# SX1276Radio.net
KiCad netlist of a schematic drawn in Altium Designer
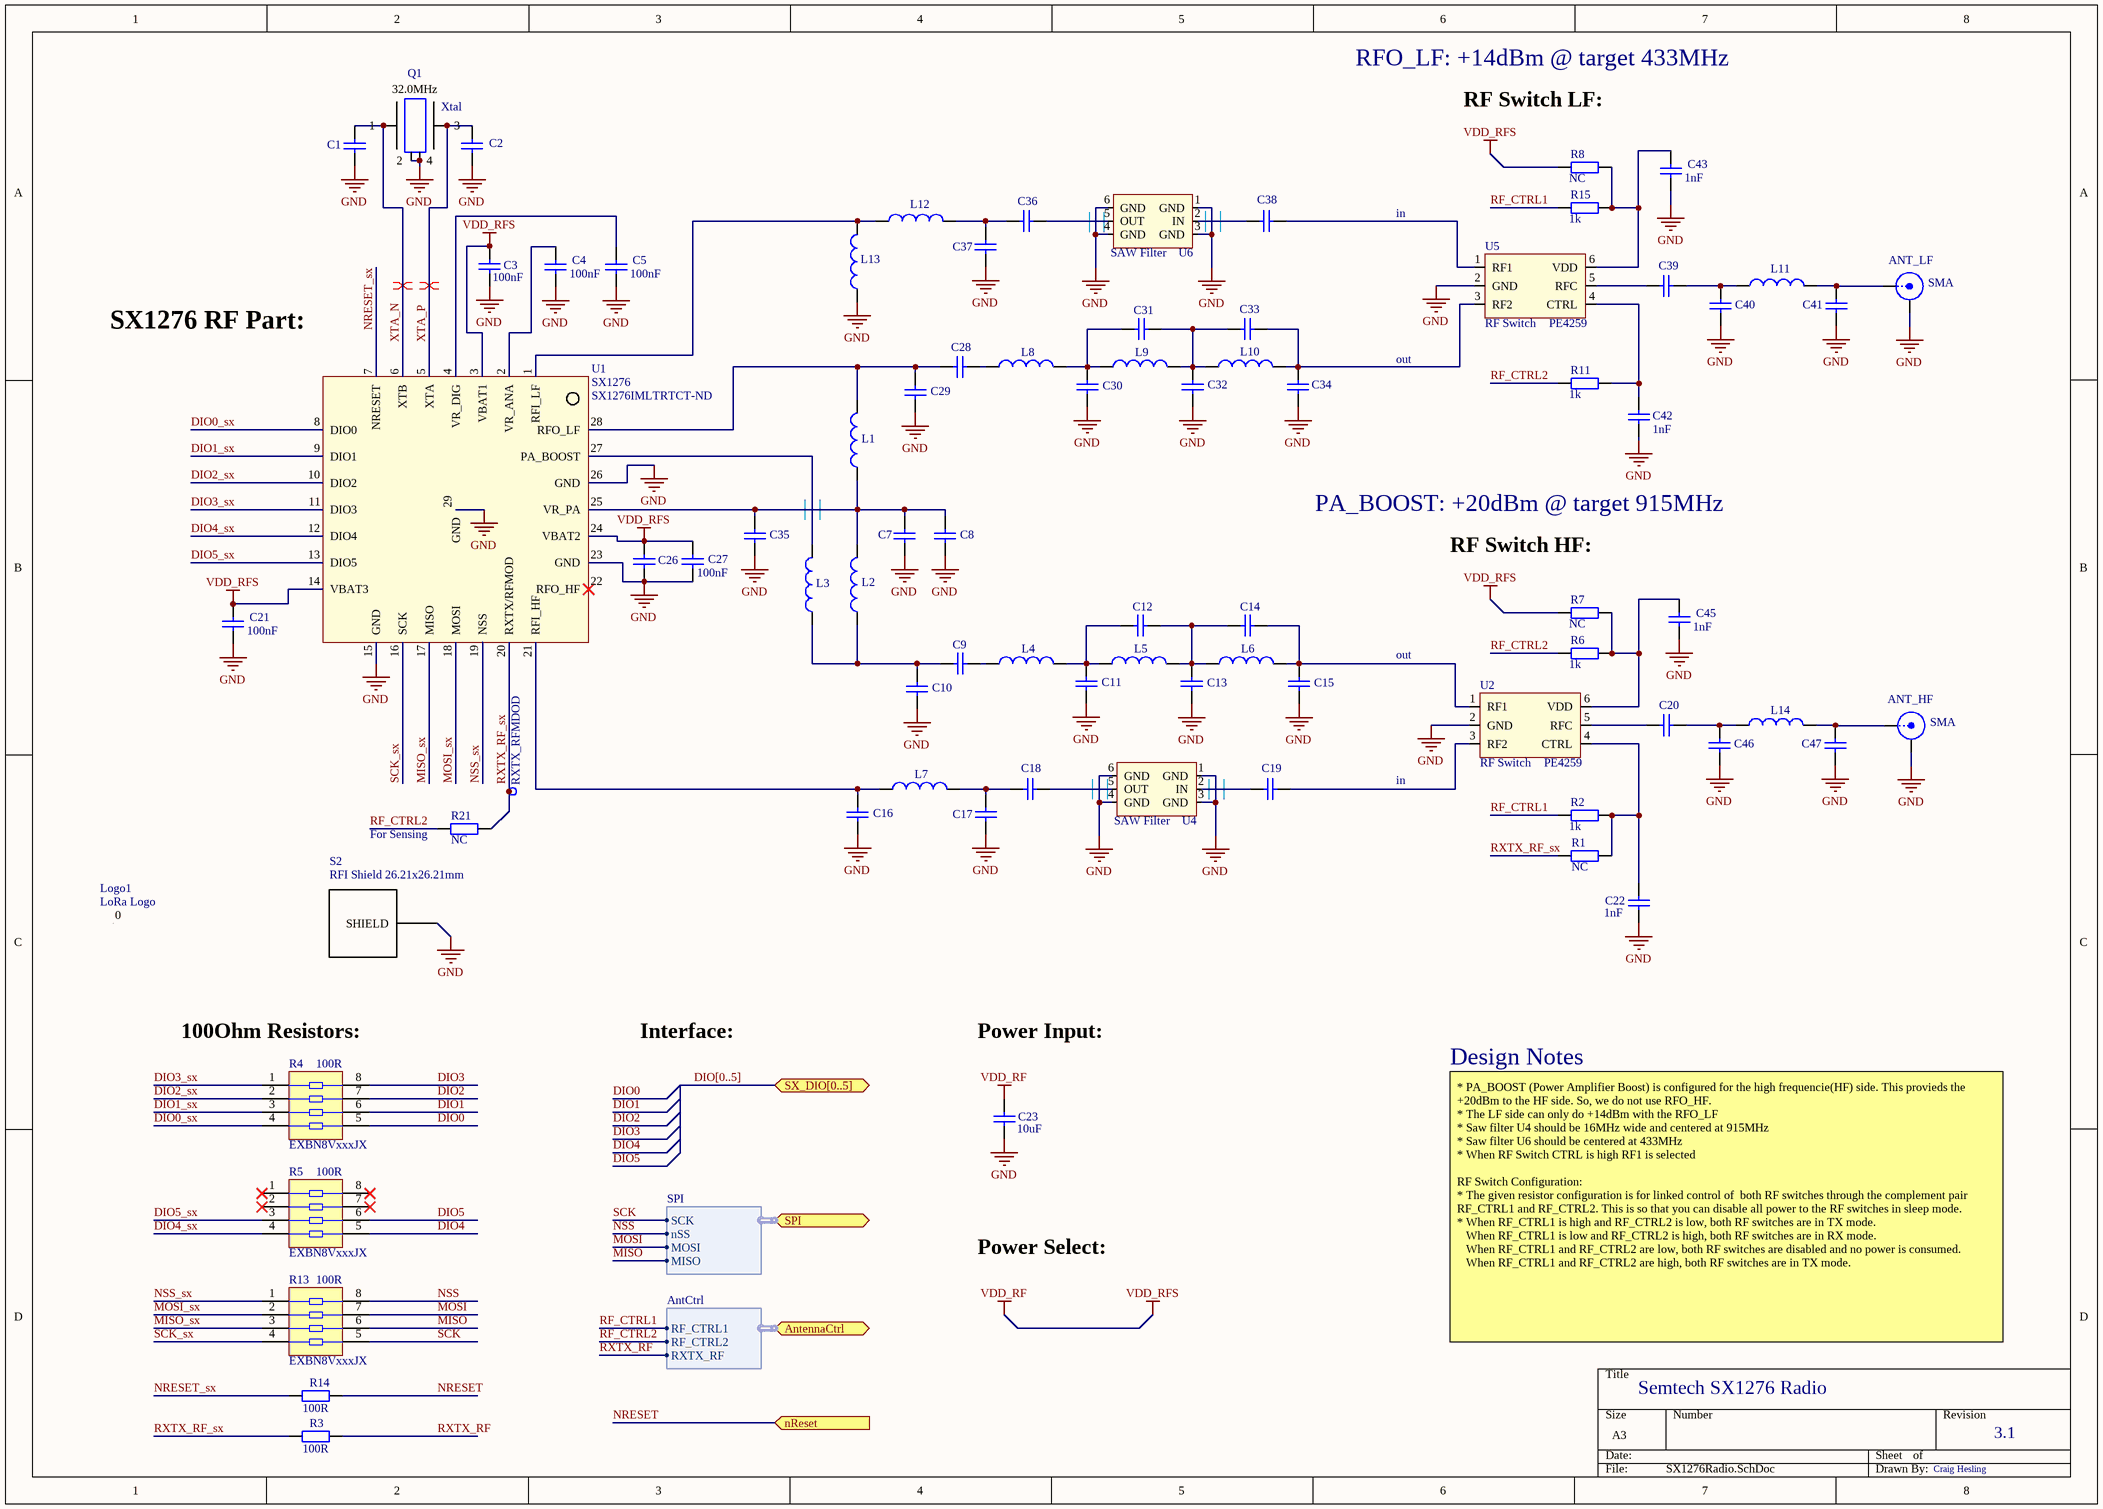
[diagram p0: SX1276Radio.SchDoc]

(export (version "E")
  (design (tool "Eeschema 10.0.6"))
  (components
    (comp (ref "ANT_HF")
      (value "SMA")
      (footprint "SMA END LAUNCH JACK RECEPTACLE SHORT")
      (description "SMA Straight Connector")
      (fields (field (name "PUBLISHER") "Altium Limited"))
      (libsource (lib "SX1276_e268v01a") (part "SMA"))
    )
    (comp (ref "ANT_LF")
      (value "SMA")
      (footprint "SMA END LAUNCH JACK RECEPTACLE SHORT")
      (description "SMA Straight Connector")
      (fields (field (name "PUBLISHER") "Altium Limited"))
      (libsource (lib "SX1276_e268v01a") (part "SMA"))
    )
    (comp (ref "C1")
      (value "Cap")
      (footprint "rlc_402_smd")
      (description "Capacitor SMD")
      (fields (field (name "PUBLISHER") "Altium Limited"))
      (libsource (lib "SX1276_e268v01a") (part "Cap"))
    )
    (comp (ref "C2")
      (value "Cap")
      (footprint "rlc_402_smd")
      (description "Capacitor SMD")
      (fields (field (name "PUBLISHER") "Altium Limited"))
      (libsource (lib "SX1276_e268v01a") (part "Cap"))
    )
    (comp (ref "C3")
      (value "100nF")
      (footprint "rlc_402_smd")
      (description "Capacitor SMD")
      (fields (field (name "Comment") "Cap") (field (name "PUBLISHER") "Altium Limited"))
      (libsource (lib "SX1276_e268v01a") (part "Cap"))
    )
    (comp (ref "C4")
      (value "100nF")
      (footprint "rlc_402_smd")
      (description "Capacitor SMD")
      (fields (field (name "Comment") "Cap") (field (name "PUBLISHER") "Altium Limited"))
      (libsource (lib "SX1276_e268v01a") (part "Cap"))
    )
    (comp (ref "C5")
      (value "100nF")
      (footprint "rlc_402_smd")
      (description "Capacitor SMD")
      (fields (field (name "Comment") "Cap") (field (name "PUBLISHER") "Altium Limited"))
      (libsource (lib "SX1276_e268v01a") (part "Cap"))
    )
    (comp (ref "C7")
      (value "Cap")
      (footprint "rlc_402_smd")
      (description "Capacitor SMD")
      (fields (field (name "PUBLISHER") "Altium Limited"))
      (libsource (lib "SX1276_e268v01a") (part "Cap"))
    )
    (comp (ref "C8")
      (value "Cap")
      (footprint "rlc_402_smd")
      (description "Capacitor SMD")
      (fields (field (name "PUBLISHER") "Altium Limited"))
      (libsource (lib "SX1276_e268v01a") (part "Cap"))
    )
    (comp (ref "C9")
      (value "Cap")
      (footprint "rlc_402_smd")
      (description "Capacitor SMD")
      (fields (field (name "PUBLISHER") "Altium Limited"))
      (libsource (lib "SX1276_e268v01a") (part "Cap"))
    )
    (comp (ref "C10")
      (value "Cap")
      (footprint "rlc_402_smd")
      (description "Capacitor SMD")
      (fields (field (name "PUBLISHER") "Altium Limited"))
      (libsource (lib "SX1276_e268v01a") (part "Cap"))
    )
    (comp (ref "C11")
      (value "Cap")
      (footprint "rlc_402_smd")
      (description "Capacitor SMD")
      (fields (field (name "PUBLISHER") "Altium Limited"))
      (libsource (lib "SX1276_e268v01a") (part "Cap"))
    )
    (comp (ref "C12")
      (value "Cap")
      (footprint "rlc_402_smd")
      (description "Capacitor SMD")
      (fields (field (name "PUBLISHER") "Altium Limited"))
      (libsource (lib "SX1276_e268v01a") (part "Cap"))
    )
    (comp (ref "C13")
      (value "Cap")
      (footprint "rlc_402_smd")
      (description "Capacitor SMD")
      (fields (field (name "PUBLISHER") "Altium Limited"))
      (libsource (lib "SX1276_e268v01a") (part "Cap"))
    )
    (comp (ref "C14")
      (value "Cap")
      (footprint "rlc_402_smd")
      (description "Capacitor SMD")
      (fields (field (name "PUBLISHER") "Altium Limited"))
      (libsource (lib "SX1276_e268v01a") (part "Cap"))
    )
    (comp (ref "C15")
      (value "Cap")
      (footprint "rlc_402_smd")
      (description "Capacitor SMD")
      (fields (field (name "PUBLISHER") "Altium Limited"))
      (libsource (lib "SX1276_e268v01a") (part "Cap"))
    )
    (comp (ref "C16")
      (value "Cap")
      (footprint "rlc_402_smd")
      (description "Capacitor SMD")
      (fields (field (name "PUBLISHER") "Altium Limited"))
      (libsource (lib "SX1276_e268v01a") (part "Cap"))
    )
    (comp (ref "C17")
      (value "Cap")
      (footprint "rlc_402_smd")
      (description "Capacitor SMD")
      (fields (field (name "PUBLISHER") "Altium Limited"))
      (libsource (lib "SX1276_e268v01a") (part "Cap"))
    )
    (comp (ref "C18")
      (value "Cap")
      (footprint "rlc_402_smd")
      (description "Capacitor SMD")
      (fields (field (name "PUBLISHER") "Altium Limited"))
      (libsource (lib "SX1276_e268v01a") (part "Cap"))
    )
    (comp (ref "C19")
      (value "Cap")
      (footprint "rlc_402_smd")
      (description "Capacitor SMD")
      (fields (field (name "PUBLISHER") "Altium Limited"))
      (libsource (lib "SX1276_e268v01a") (part "Cap"))
    )
    (comp (ref "C20")
      (value "Cap")
      (footprint "rlc_402_smd")
      (description "Capacitor SMD")
      (fields (field (name "PUBLISHER") "Altium Limited"))
      (libsource (lib "SX1276_e268v01a") (part "Cap"))
    )
    (comp (ref "C21")
      (value "100nF")
      (footprint "rlc_402_smd")
      (description "Capacitor SMD")
      (fields (field (name "Comment") "Cap") (field (name "PUBLISHER") "Altium Limited"))
      (libsource (lib "SX1276_e268v01a") (part "Cap"))
    )
    (comp (ref "C22")
      (value "1nF")
      (footprint "rlc_402_smd")
      (description "Capacitor SMD")
      (fields (field (name "Comment") "Cap") (field (name "PUBLISHER") "Altium Limited"))
      (libsource (lib "SX1276_e268v01a") (part "Cap"))
    )
    (comp (ref "C23")
      (value "10uF")
      (footprint "rlc_805_smd")
      (description "Capacitor SMD")
      (fields (field (name "Comment") "Cap") (field (name "PUBLISHER") "Altium Limited"))
      (libsource (lib "SX1276_e268v01a") (part "Cap"))
    )
    (comp (ref "C26")
      (value "Cap")
      (footprint "rlc_402_smd")
      (description "Capacitor SMD")
      (fields (field (name "PUBLISHER") "Altium Limited"))
      (libsource (lib "SX1276_e268v01a") (part "Cap"))
    )
    (comp (ref "C27")
      (value "100nF")
      (footprint "rlc_402_smd")
      (description "Capacitor SMD")
      (fields (field (name "Comment") "Cap") (field (name "PUBLISHER") "Altium Limited"))
      (libsource (lib "SX1276_e268v01a") (part "Cap"))
    )
    (comp (ref "C28")
      (value "Cap")
      (footprint "rlc_402_smd")
      (description "Capacitor SMD")
      (fields (field (name "PUBLISHER") "Altium Limited"))
      (libsource (lib "SX1276_e268v01a") (part "Cap"))
    )
    (comp (ref "C29")
      (value "Cap")
      (footprint "rlc_402_smd")
      (description "Capacitor SMD")
      (fields (field (name "PUBLISHER") "Altium Limited"))
      (libsource (lib "SX1276_e268v01a") (part "Cap"))
    )
    (comp (ref "C30")
      (value "Cap")
      (footprint "rlc_402_smd")
      (description "Capacitor SMD")
      (fields (field (name "PUBLISHER") "Altium Limited"))
      (libsource (lib "SX1276_e268v01a") (part "Cap"))
    )
    (comp (ref "C31")
      (value "Cap")
      (footprint "rlc_402_smd")
      (description "Capacitor SMD")
      (fields (field (name "PUBLISHER") "Altium Limited"))
      (libsource (lib "SX1276_e268v01a") (part "Cap"))
    )
    (comp (ref "C32")
      (value "Cap")
      (footprint "rlc_402_smd")
      (description "Capacitor SMD")
      (fields (field (name "PUBLISHER") "Altium Limited"))
      (libsource (lib "SX1276_e268v01a") (part "Cap"))
    )
    (comp (ref "C33")
      (value "Cap")
      (footprint "rlc_402_smd")
      (description "Capacitor SMD")
      (fields (field (name "PUBLISHER") "Altium Limited"))
      (libsource (lib "SX1276_e268v01a") (part "Cap"))
    )
    (comp (ref "C34")
      (value "Cap")
      (footprint "rlc_402_smd")
      (description "Capacitor SMD")
      (fields (field (name "PUBLISHER") "Altium Limited"))
      (libsource (lib "SX1276_e268v01a") (part "Cap"))
    )
    (comp (ref "C35")
      (value "Cap")
      (footprint "rlc_402_smd")
      (description "Capacitor SMD")
      (fields (field (name "PUBLISHER") "Altium Limited"))
      (libsource (lib "SX1276_e268v01a") (part "Cap"))
    )
    (comp (ref "C36")
      (value "Cap")
      (footprint "rlc_402_smd")
      (description "Capacitor SMD")
      (fields (field (name "PUBLISHER") "Altium Limited"))
      (libsource (lib "SX1276_e268v01a") (part "Cap"))
    )
    (comp (ref "C37")
      (value "Cap")
      (footprint "rlc_402_smd")
      (description "Capacitor SMD")
      (fields (field (name "PUBLISHER") "Altium Limited"))
      (libsource (lib "SX1276_e268v01a") (part "Cap"))
    )
    (comp (ref "C38")
      (value "Cap")
      (footprint "rlc_402_smd")
      (description "Capacitor SMD")
      (fields (field (name "PUBLISHER") "Altium Limited"))
      (libsource (lib "SX1276_e268v01a") (part "Cap"))
    )
    (comp (ref "C39")
      (value "Cap")
      (footprint "rlc_402_smd")
      (description "Capacitor SMD")
      (fields (field (name "PUBLISHER") "Altium Limited"))
      (libsource (lib "SX1276_e268v01a") (part "Cap"))
    )
    (comp (ref "C40")
      (value "Cap")
      (footprint "rlc_402_smd")
      (description "Capacitor SMD")
      (fields (field (name "PUBLISHER") "Altium Limited"))
      (libsource (lib "SX1276_e268v01a") (part "Cap"))
    )
    (comp (ref "C41")
      (value "Cap")
      (footprint "rlc_402_smd")
      (description "Capacitor SMD")
      (fields (field (name "PUBLISHER") "Altium Limited"))
      (libsource (lib "SX1276_e268v01a") (part "Cap"))
    )
    (comp (ref "C42")
      (value "1nF")
      (footprint "rlc_402_smd")
      (description "Capacitor SMD")
      (fields (field (name "Comment") "Cap") (field (name "PUBLISHER") "Altium Limited"))
      (libsource (lib "SX1276_e268v01a") (part "Cap"))
    )
    (comp (ref "C43")
      (value "1nF")
      (footprint "rlc_402_smd")
      (description "Capacitor SMD")
      (fields (field (name "Comment") "Cap") (field (name "PUBLISHER") "Altium Limited"))
      (libsource (lib "SX1276_e268v01a") (part "Cap"))
    )
    (comp (ref "C45")
      (value "1nF")
      (footprint "rlc_402_smd")
      (description "Capacitor SMD")
      (fields (field (name "Comment") "Cap") (field (name "PUBLISHER") "Altium Limited"))
      (libsource (lib "SX1276_e268v01a") (part "Cap"))
    )
    (comp (ref "C46")
      (value "Cap")
      (footprint "rlc_402_smd")
      (description "Capacitor SMD")
      (fields (field (name "PUBLISHER") "Altium Limited"))
      (libsource (lib "SX1276_e268v01a") (part "Cap"))
    )
    (comp (ref "C47")
      (value "Cap")
      (footprint "rlc_402_smd")
      (description "Capacitor SMD")
      (fields (field (name "PUBLISHER") "Altium Limited"))
      (libsource (lib "SX1276_e268v01a") (part "Cap"))
    )
    (comp (ref "L1")
      (value "Inductor")
      (footprint "rlc_402_smd")
      (description "Inductor SMD")
      (fields (field (name "PUBLISHER") "Altium Limited"))
      (libsource (lib "SX1276_e268v01a") (part "Inductor"))
    )
    (comp (ref "L2")
      (value "Inductor")
      (footprint "rlc_402_smd")
      (description "Inductor SMD")
      (fields (field (name "PUBLISHER") "Altium Limited"))
      (libsource (lib "SX1276_e268v01a") (part "Inductor"))
    )
    (comp (ref "L3")
      (value "Inductor")
      (footprint "rlc_402_smd")
      (description "Inductor SMD")
      (fields (field (name "PUBLISHER") "Altium Limited"))
      (libsource (lib "SX1276_e268v01a") (part "Inductor"))
    )
    (comp (ref "L4")
      (value "Inductor")
      (footprint "rlc_402_smd")
      (description "Inductor SMD")
      (fields (field (name "PUBLISHER") "Altium Limited"))
      (libsource (lib "SX1276_e268v01a") (part "Inductor"))
    )
    (comp (ref "L5")
      (value "Inductor")
      (footprint "rlc_402_smd")
      (description "Inductor SMD")
      (fields (field (name "PUBLISHER") "Altium Limited"))
      (libsource (lib "SX1276_e268v01a") (part "Inductor"))
    )
    (comp (ref "L6")
      (value "Inductor")
      (footprint "rlc_402_smd")
      (description "Inductor SMD")
      (fields (field (name "PUBLISHER") "Altium Limited"))
      (libsource (lib "SX1276_e268v01a") (part "Inductor"))
    )
    (comp (ref "L7")
      (value "Inductor")
      (footprint "rlc_402_smd")
      (description "Inductor SMD")
      (fields (field (name "PUBLISHER") "Altium Limited"))
      (libsource (lib "SX1276_e268v01a") (part "Inductor"))
    )
    (comp (ref "L8")
      (value "Inductor")
      (footprint "rlc_402_smd")
      (description "Inductor SMD")
      (fields (field (name "PUBLISHER") "Altium Limited"))
      (libsource (lib "SX1276_e268v01a") (part "Inductor"))
    )
    (comp (ref "L9")
      (value "Inductor")
      (footprint "rlc_402_smd")
      (description "Inductor SMD")
      (fields (field (name "PUBLISHER") "Altium Limited"))
      (libsource (lib "SX1276_e268v01a") (part "Inductor"))
    )
    (comp (ref "L10")
      (value "Inductor")
      (footprint "rlc_402_smd")
      (description "Inductor SMD")
      (fields (field (name "PUBLISHER") "Altium Limited"))
      (libsource (lib "SX1276_e268v01a") (part "Inductor"))
    )
    (comp (ref "L11")
      (value "Inductor")
      (footprint "rlc_402_smd")
      (description "Inductor SMD")
      (fields (field (name "PUBLISHER") "Altium Limited"))
      (libsource (lib "SX1276_e268v01a") (part "Inductor"))
    )
    (comp (ref "L12")
      (value "Inductor")
      (footprint "rlc_402_smd")
      (description "Inductor SMD")
      (fields (field (name "PUBLISHER") "Altium Limited"))
      (libsource (lib "SX1276_e268v01a") (part "Inductor"))
    )
    (comp (ref "L13")
      (value "Inductor")
      (footprint "rlc_402_smd")
      (description "Inductor SMD")
      (fields (field (name "PUBLISHER") "Altium Limited"))
      (libsource (lib "SX1276_e268v01a") (part "Inductor"))
    )
    (comp (ref "L14")
      (value "Inductor")
      (footprint "rlc_402_smd")
      (description "Inductor SMD")
      (fields (field (name "PUBLISHER") "Altium Limited"))
      (libsource (lib "SX1276_e268v01a") (part "Inductor"))
    )
    (comp (ref "Logo1")
      (value "LoRa Logo")
      (footprint "Logo LoRa Size1")
      (description "Schematic symbol for Logo")
      (libsource (lib "SX1276_e268v01a") (part "Logo"))
    )
    (comp (ref "Q1")
      (value "Xtal")
      (footprint "nd3225da - nd2520da")
      (description "Crystal with GND pins")
      (fields (field (name "ALTIUM_VALUE") "32.0MHz"))
      (libsource (lib "SX1276_e268v01a") (part "Xtal GND"))
    )
    (comp (ref "R1")
      (value "NC")
      (footprint "rlc_402_smd")
      (description "Resistor SMD - IEC symbol version")
      (fields (field (name "Comment") "Resistor"))
      (libsource (lib "") (part "Resistor_2"))
    )
    (comp (ref "R2")
      (value "1k")
      (footprint "rlc_402_smd")
      (description "Resistor SMD - IEC symbol version")
      (fields (field (name "Comment") "Resistor"))
      (libsource (lib "SX1276_e268v01a") (part "Resistor"))
    )
    (comp (ref "R3")
      (value "100R")
      (footprint "rlc_402_smd")
      (description "Resistor SMD - IEC symbol version")
      (fields (field (name "Comment") "Resistor"))
      (libsource (lib "") (part "Resistor_1"))
    )
    (comp (ref "R4")
      (value "EXBN8VxxxJX")
      (footprint "EXB28V")
      (description "Mini-Flat Package, Isolated Resistor Network, 0.031 W/resistor")
      (fields (field (name "ALTIUM_VALUE") "100R"))
      (libsource (lib "SX1276_e268v01a") (part "EXBN8VxxxJX"))
    )
    (comp (ref "R5")
      (value "EXBN8VxxxJX")
      (footprint "EXB28V")
      (description "Mini-Flat Package, Isolated Resistor Network, 0.031 W/resistor")
      (fields (field (name "ALTIUM_VALUE") "100R"))
      (libsource (lib "SX1276_e268v01a") (part "EXBN8VxxxJX"))
    )
    (comp (ref "R6")
      (value "1k")
      (footprint "rlc_402_smd")
      (description "Resistor SMD - IEC symbol version")
      (fields (field (name "Comment") "Resistor"))
      (libsource (lib "SX1276_e268v01a") (part "Resistor"))
    )
    (comp (ref "R7")
      (value "NC")
      (footprint "rlc_402_smd")
      (description "Resistor SMD - IEC symbol version")
      (fields (field (name "Comment") "Resistor"))
      (libsource (lib "SX1276_e268v01a") (part "Resistor"))
    )
    (comp (ref "R8")
      (value "NC")
      (footprint "rlc_402_smd")
      (description "Resistor SMD - IEC symbol version")
      (fields (field (name "Comment") "Resistor"))
      (libsource (lib "SX1276_e268v01a") (part "Resistor"))
    )
    (comp (ref "R11")
      (value "1k")
      (footprint "rlc_402_smd")
      (description "Resistor SMD - IEC symbol version")
      (fields (field (name "Comment") "Resistor"))
      (libsource (lib "SX1276_e268v01a") (part "Resistor"))
    )
    (comp (ref "R13")
      (value "EXBN8VxxxJX")
      (footprint "EXB28V")
      (description "Mini-Flat Package, Isolated Resistor Network, 0.031 W/resistor")
      (fields (field (name "ALTIUM_VALUE") "100R"))
      (libsource (lib "SX1276_e268v01a") (part "EXBN8VxxxJX"))
    )
    (comp (ref "R14")
      (value "100R")
      (footprint "rlc_402_smd")
      (description "Resistor SMD - IEC symbol version")
      (fields (field (name "Comment") "Resistor"))
      (libsource (lib "") (part "Resistor_1"))
    )
    (comp (ref "R15")
      (value "1k")
      (footprint "rlc_402_smd")
      (description "Resistor SMD - IEC symbol version")
      (fields (field (name "Comment") "Resistor"))
      (libsource (lib "SX1276_e268v01a") (part "Resistor"))
    )
    (comp (ref "R21")
      (value "NC")
      (footprint "rlc_402_smd")
      (description "Resistor SMD - IEC symbol version")
      (fields (field (name "Comment") "Resistor"))
      (libsource (lib "SX1276_e268v01a") (part "Resistor"))
    )
    (comp (ref "RXTX_RFMDOD")
      (value "Test Pin")
      (footprint "pin_SMD")
      (libsource (lib "SX1276_e268v01a") (part "test_pin"))
    )
    (comp (ref "S2")
      (value "RFI Shield 26.21x26.21mm")
      (footprint "RFI_SHIELD_26.21x26.21MM_Padded")
      (libsource (lib "ExtraComponents") (part "RFI_SHIELD_26.21x26.21mm"))
    )
    (comp (ref "U1")
      (value "SX1276")
      (footprint "vqfn28_6x6mm_big_vias")
      (description "SX1276 - Low Power Integrated UHF Transceiver with loRa Modem")
      (fields (field (name "SUPPLIER PART NUMBER 1") "SX1276IMLTRTCT-ND"))
      (libsource (lib "SX1276_e268v01a") (part "SX1276"))
    )
    (comp (ref "U2")
      (value "RF Switch")
      (footprint "SC70-6")
      (description "PE4259 Peregrine RF Switch")
      (fields (field (name "ALTIUM_VALUE") "PE4259"))
      (libsource (lib "SX1276_e268v01a") (part "PE4259 RF Switch"))
    )
    (comp (ref "U4")
      (value "SAW Filter")
      (footprint "DCC6C_3.0x3.0mm")
      (description "SAW Filter - Bandpass - TEMEX type")
      (libsource (lib "SX1276_e268v01a") (part "SAW Filter"))
    )
    (comp (ref "U5")
      (value "RF Switch")
      (footprint "SC70-6")
      (description "PE4259 Peregrine RF Switch")
      (fields (field (name "ALTIUM_VALUE") "PE4259"))
      (libsource (lib "SX1276_e268v01a") (part "PE4259 RF Switch"))
    )
    (comp (ref "U6")
      (value "SAW Filter")
      (footprint "DCC6C_3.0x3.0mm")
      (description "SAW Filter - Bandpass - TEMEX type")
      (libsource (lib "SX1276_e268v01a") (part "SAW Filter"))
    )
  )
  (nets
    (net (code "3") (name "/DIO0") (class "Default")
      (node (ref "R4") (pin "5") (pinfunction "5_5") (pintype "passive"))
    )
    (net (code "4") (name "/DIO0_sx") (class "Default")
      (node (ref "R4") (pin "4") (pinfunction "4_4") (pintype "passive"))
      (node (ref "U1") (pin "8") (pinfunction "DIO0_8") (pintype "passive"))
    )
    (net (code "5") (name "/DIO1") (class "Default")
      (node (ref "R4") (pin "6") (pinfunction "6_6") (pintype "passive"))
    )
    (net (code "6") (name "/DIO1_sx") (class "Default")
      (node (ref "R4") (pin "3") (pinfunction "3_3") (pintype "passive"))
      (node (ref "U1") (pin "9") (pinfunction "DIO1_9") (pintype "passive"))
    )
    (net (code "7") (name "/DIO2") (class "Default")
      (node (ref "R4") (pin "7") (pinfunction "7_7") (pintype "passive"))
    )
    (net (code "8") (name "/DIO2_sx") (class "Default")
      (node (ref "R4") (pin "2") (pinfunction "2_2") (pintype "passive"))
      (node (ref "U1") (pin "10") (pinfunction "DIO2_10") (pintype "passive"))
    )
    (net (code "9") (name "/DIO3") (class "Default")
      (node (ref "R4") (pin "8") (pinfunction "8_8") (pintype "passive"))
    )
    (net (code "10") (name "/DIO3_sx") (class "Default")
      (node (ref "R4") (pin "1") (pinfunction "1_1") (pintype "passive"))
      (node (ref "U1") (pin "11") (pinfunction "DIO3_11") (pintype "passive"))
    )
    (net (code "11") (name "/DIO4") (class "Default")
      (node (ref "R5") (pin "5") (pinfunction "5_5") (pintype "passive"))
    )
    (net (code "12") (name "/DIO4_sx") (class "Default")
      (node (ref "R5") (pin "4") (pinfunction "4_4") (pintype "passive"))
      (node (ref "U1") (pin "12") (pinfunction "DIO4_12") (pintype "passive"))
    )
    (net (code "13") (name "/DIO5") (class "Default")
      (node (ref "R5") (pin "6") (pinfunction "6_6") (pintype "passive"))
    )
    (net (code "14") (name "/DIO5_sx") (class "Default")
      (node (ref "R5") (pin "3") (pinfunction "3_3") (pintype "passive"))
      (node (ref "U1") (pin "13") (pinfunction "DIO5_13") (pintype "passive"))
    )
    (net (code "16") (name "/MISO") (class "Default")
      (node (ref "R13") (pin "6") (pinfunction "6_6") (pintype "passive"))
    )
    (net (code "17") (name "/MISO_sx") (class "Default")
      (node (ref "R13") (pin "3") (pinfunction "3_3") (pintype "passive"))
      (node (ref "U1") (pin "17") (pinfunction "MISO_17") (pintype "passive"))
    )
    (net (code "18") (name "/MOSI") (class "Default")
      (node (ref "R13") (pin "7") (pinfunction "7_7") (pintype "passive"))
    )
    (net (code "19") (name "/MOSI_sx") (class "Default")
      (node (ref "R13") (pin "2") (pinfunction "2_2") (pintype "passive"))
      (node (ref "U1") (pin "18") (pinfunction "MOSI_18") (pintype "passive"))
    )
    (net (code "20") (name "/NRESET") (class "Default")
      (node (ref "R14") (pin "2") (pinfunction "2_2") (pintype "passive"))
    )
    (net (code "21") (name "/NRESET_sx") (class "Default")
      (node (ref "R14") (pin "1") (pinfunction "1_1") (pintype "passive"))
      (node (ref "U1") (pin "7") (pinfunction "NRESET_7") (pintype "passive"))
    )
    (net (code "22") (name "/NSS") (class "Default")
      (node (ref "R13") (pin "8") (pinfunction "8_8") (pintype "passive"))
    )
    (net (code "23") (name "/NSS_sx") (class "Default")
      (node (ref "R13") (pin "1") (pinfunction "1_1") (pintype "passive"))
      (node (ref "U1") (pin "19") (pinfunction "NSS_19") (pintype "passive"))
    )
    (net (code "24") (name "/RF_CTRL1") (class "Default")
      (node (ref "R15") (pin "2") (pinfunction "2_2") (pintype "passive"))
      (node (ref "R2") (pin "2") (pinfunction "2_2") (pintype "passive"))
    )
    (net (code "25") (name "/RF_CTRL2") (class "Default")
      (node (ref "R11") (pin "2") (pinfunction "2_2") (pintype "passive"))
      (node (ref "R21") (pin "2") (pinfunction "2_2") (pintype "passive"))
      (node (ref "R6") (pin "2") (pinfunction "2_2") (pintype "passive"))
    )
    (net (code "26") (name "/RXTX_RF") (class "Default")
      (node (ref "R3") (pin "2") (pinfunction "2_2") (pintype "passive"))
    )
    (net (code "27") (name "/RXTX_RF_sx") (class "Default")
      (node (ref "R1") (pin "1") (pinfunction "1_1") (pintype "passive"))
      (node (ref "R21") (pin "1") (pinfunction "1_1") (pintype "passive"))
      (node (ref "R3") (pin "1") (pinfunction "1_1") (pintype "passive"))
      (node (ref "RXTX_RFMDOD") (pin "1") (pinfunction "pin_1") (pintype "passive"))
      (node (ref "U1") (pin "20") (pinfunction "RXTX/RFMOD_20") (pintype "passive"))
    )
    (net (code "28") (name "/SCK") (class "Default")
      (node (ref "R13") (pin "5") (pinfunction "5_5") (pintype "passive"))
    )
    (net (code "29") (name "/SCK_sx") (class "Default")
      (node (ref "R13") (pin "4") (pinfunction "4_4") (pintype "passive"))
      (node (ref "U1") (pin "16") (pinfunction "SCK_16") (pintype "passive"))
    )
    (net (code "30") (name "/XTA_N") (class "Default")
      (node (ref "C1") (pin "2") (pinfunction "2_2") (pintype "passive"))
      (node (ref "Q1") (pin "1") (pinfunction "1_1") (pintype "passive"))
      (node (ref "U1") (pin "6") (pinfunction "XTB_6") (pintype "passive"))
    )
    (net (code "31") (name "/XTA_P") (class "Default")
      (node (ref "C2") (pin "2") (pinfunction "2_2") (pintype "passive"))
      (node (ref "Q1") (pin "3") (pinfunction "3_3") (pintype "passive"))
      (node (ref "U1") (pin "5") (pinfunction "XTA_5") (pintype "passive"))
    )
    (net (code "34") (name "GND") (class "Default")
      (node (ref "ANT_HF") (pin "2") (pinfunction "GND_2") (pintype "passive"))
      (node (ref "ANT_LF") (pin "2") (pinfunction "GND_2") (pintype "passive"))
      (node (ref "C1") (pin "1") (pinfunction "1_1") (pintype "passive"))
      (node (ref "C10") (pin "1") (pinfunction "1_1") (pintype "passive"))
      (node (ref "C11") (pin "1") (pinfunction "1_1") (pintype "passive"))
      (node (ref "C13") (pin "1") (pinfunction "1_1") (pintype "passive"))
      (node (ref "C15") (pin "1") (pinfunction "1_1") (pintype "passive"))
      (node (ref "C16") (pin "1") (pinfunction "1_1") (pintype "passive"))
      (node (ref "C17") (pin "1") (pinfunction "1_1") (pintype "passive"))
      (node (ref "C2") (pin "1") (pinfunction "1_1") (pintype "passive"))
      (node (ref "C21") (pin "1") (pinfunction "1_1") (pintype "passive"))
      (node (ref "C22") (pin "2") (pinfunction "2_2") (pintype "passive"))
      (node (ref "C23") (pin "1") (pinfunction "1_1") (pintype "passive"))
      (node (ref "C26") (pin "1") (pinfunction "1_1") (pintype "passive"))
      (node (ref "C27") (pin "1") (pinfunction "1_1") (pintype "passive"))
      (node (ref "C29") (pin "1") (pinfunction "1_1") (pintype "passive"))
      (node (ref "C3") (pin "1") (pinfunction "1_1") (pintype "passive"))
      (node (ref "C30") (pin "1") (pinfunction "1_1") (pintype "passive"))
      (node (ref "C32") (pin "1") (pinfunction "1_1") (pintype "passive"))
      (node (ref "C34") (pin "1") (pinfunction "1_1") (pintype "passive"))
      (node (ref "C35") (pin "1") (pinfunction "1_1") (pintype "passive"))
      (node (ref "C37") (pin "1") (pinfunction "1_1") (pintype "passive"))
      (node (ref "C4") (pin "1") (pinfunction "1_1") (pintype "passive"))
      (node (ref "C40") (pin "1") (pinfunction "1_1") (pintype "passive"))
      (node (ref "C41") (pin "1") (pinfunction "1_1") (pintype "passive"))
      (node (ref "C42") (pin "2") (pinfunction "2_2") (pintype "passive"))
      (node (ref "C43") (pin "1") (pinfunction "1_1") (pintype "passive"))
      (node (ref "C45") (pin "1") (pinfunction "1_1") (pintype "passive"))
      (node (ref "C46") (pin "1") (pinfunction "1_1") (pintype "passive"))
      (node (ref "C47") (pin "1") (pinfunction "1_1") (pintype "passive"))
      (node (ref "C5") (pin "1") (pinfunction "1_1") (pintype "passive"))
      (node (ref "C7") (pin "1") (pinfunction "1_1") (pintype "passive"))
      (node (ref "C8") (pin "1") (pinfunction "1_1") (pintype "passive"))
      (node (ref "L13") (pin "1") (pinfunction "1_1") (pintype "passive"))
      (node (ref "Q1") (pin "2") (pinfunction "2_2") (pintype "passive"))
      (node (ref "Q1") (pin "4") (pinfunction "4_4") (pintype "passive"))
      (node (ref "S2") (pin "SHIELD") (pinfunction "SHIELD_SHIELD") (pintype "passive"))
      (node (ref "U1") (pin "15") (pinfunction "GND_15") (pintype "passive"))
      (node (ref "U1") (pin "23") (pinfunction "GND_23") (pintype "passive"))
      (node (ref "U1") (pin "26") (pinfunction "GND_26") (pintype "passive"))
      (node (ref "U1") (pin "29") (pinfunction "GND_29") (pintype "passive"))
      (node (ref "U2") (pin "2") (pinfunction "GND_2") (pintype "passive"))
      (node (ref "U4") (pin "1") (pinfunction "GND_1") (pintype "passive"))
      (node (ref "U4") (pin "3") (pinfunction "GND_3") (pintype "passive"))
      (node (ref "U4") (pin "4") (pinfunction "GND_4") (pintype "passive"))
      (node (ref "U4") (pin "6") (pinfunction "GND_6") (pintype "passive"))
      (node (ref "U5") (pin "2") (pinfunction "GND_2") (pintype "passive"))
      (node (ref "U6") (pin "1") (pinfunction "GND_1") (pintype "passive"))
      (node (ref "U6") (pin "3") (pinfunction "GND_3") (pintype "passive"))
      (node (ref "U6") (pin "4") (pinfunction "GND_4") (pintype "passive"))
      (node (ref "U6") (pin "6") (pinfunction "GND_6") (pintype "passive"))
    )
    (net (code "35") (name "Net-(ANT_HF-Signal)") (class "Default")
      (node (ref "ANT_HF") (pin "1") (pinfunction "Signal_1") (pintype "passive"))
      (node (ref "C47") (pin "2") (pinfunction "2_2") (pintype "passive"))
      (node (ref "L14") (pin "2") (pinfunction "2_2") (pintype "passive"))
    )
    (net (code "36") (name "Net-(ANT_LF-Signal)") (class "Default")
      (node (ref "ANT_LF") (pin "1") (pinfunction "Signal_1") (pintype "passive"))
      (node (ref "C41") (pin "2") (pinfunction "2_2") (pintype "passive"))
      (node (ref "L11") (pin "2") (pinfunction "2_2") (pintype "passive"))
    )
    (net (code "37") (name "Net-(C9-Pad1)") (class "Default")
      (node (ref "C9") (pin "1") (pinfunction "1_1") (pintype "passive"))
      (node (ref "L4") (pin "1") (pinfunction "1_1") (pintype "passive"))
    )
    (net (code "38") (name "Net-(C10-Pad2)") (class "Default")
      (node (ref "C10") (pin "2") (pinfunction "2_2") (pintype "passive"))
      (node (ref "C9") (pin "2") (pinfunction "2_2") (pintype "passive"))
      (node (ref "L2") (pin "1") (pinfunction "1_1") (pintype "passive"))
      (node (ref "L3") (pin "1") (pinfunction "1_1") (pintype "passive"))
    )
    (net (code "39") (name "Net-(C11-Pad2)") (class "Default")
      (node (ref "C11") (pin "2") (pinfunction "2_2") (pintype "passive"))
      (node (ref "C12") (pin "2") (pinfunction "2_2") (pintype "passive"))
      (node (ref "L4") (pin "2") (pinfunction "2_2") (pintype "passive"))
      (node (ref "L5") (pin "1") (pinfunction "1_1") (pintype "passive"))
    )
    (net (code "40") (name "Net-(C12-Pad1)") (class "Default")
      (node (ref "C12") (pin "1") (pinfunction "1_1") (pintype "passive"))
      (node (ref "C13") (pin "2") (pinfunction "2_2") (pintype "passive"))
      (node (ref "C14") (pin "2") (pinfunction "2_2") (pintype "passive"))
      (node (ref "L5") (pin "2") (pinfunction "2_2") (pintype "passive"))
      (node (ref "L6") (pin "1") (pinfunction "1_1") (pintype "passive"))
    )
    (net (code "41") (name "Net-(C17-Pad2)") (class "Default")
      (node (ref "C17") (pin "2") (pinfunction "2_2") (pintype "passive"))
      (node (ref "C18") (pin "2") (pinfunction "2_2") (pintype "passive"))
      (node (ref "L7") (pin "2") (pinfunction "2_2") (pintype "passive"))
    )
    (net (code "42") (name "Net-(C20-Pad1)") (class "Default")
      (node (ref "C20") (pin "1") (pinfunction "1_1") (pintype "passive"))
      (node (ref "C46") (pin "2") (pinfunction "2_2") (pintype "passive"))
      (node (ref "L14") (pin "1") (pinfunction "1_1") (pintype "passive"))
    )
    (net (code "43") (name "Net-(C28-Pad1)") (class "Default")
      (node (ref "C28") (pin "1") (pinfunction "1_1") (pintype "passive"))
      (node (ref "L8") (pin "1") (pinfunction "1_1") (pintype "passive"))
    )
    (net (code "44") (name "Net-(C30-Pad2)") (class "Default")
      (node (ref "C30") (pin "2") (pinfunction "2_2") (pintype "passive"))
      (node (ref "C31") (pin "2") (pinfunction "2_2") (pintype "passive"))
      (node (ref "L8") (pin "2") (pinfunction "2_2") (pintype "passive"))
      (node (ref "L9") (pin "1") (pinfunction "1_1") (pintype "passive"))
    )
    (net (code "45") (name "Net-(C31-Pad1)") (class "Default")
      (node (ref "C31") (pin "1") (pinfunction "1_1") (pintype "passive"))
      (node (ref "C32") (pin "2") (pinfunction "2_2") (pintype "passive"))
      (node (ref "C33") (pin "2") (pinfunction "2_2") (pintype "passive"))
      (node (ref "L10") (pin "1") (pinfunction "1_1") (pintype "passive"))
      (node (ref "L9") (pin "2") (pinfunction "2_2") (pintype "passive"))
    )
    (net (code "46") (name "Net-(C36-Pad2)") (class "Default")
      (node (ref "C36") (pin "2") (pinfunction "2_2") (pintype "passive"))
      (node (ref "C37") (pin "2") (pinfunction "2_2") (pintype "passive"))
      (node (ref "L12") (pin "2") (pinfunction "2_2") (pintype "passive"))
    )
    (net (code "47") (name "Net-(C39-Pad1)") (class "Default")
      (node (ref "C39") (pin "1") (pinfunction "1_1") (pintype "passive"))
      (node (ref "C40") (pin "2") (pinfunction "2_2") (pintype "passive"))
      (node (ref "L11") (pin "1") (pinfunction "1_1") (pintype "passive"))
    )
    (net (code "48") (name "Net-(U1-PA_BOOST)") (class "Default")
      (node (ref "L3") (pin "2") (pinfunction "2_2") (pintype "passive"))
      (node (ref "U1") (pin "27") (pinfunction "PA_BOOST_27") (pintype "passive"))
    )
    (net (code "49") (name "Net-(U1-RFI_HF)") (class "Default")
      (node (ref "C16") (pin "2") (pinfunction "2_2") (pintype "passive"))
      (node (ref "L7") (pin "1") (pinfunction "1_1") (pintype "passive"))
      (node (ref "U1") (pin "21") (pinfunction "RFI_HF_21") (pintype "passive"))
    )
    (net (code "50") (name "Net-(U1-RFI_LF)") (class "Default")
      (node (ref "L12") (pin "1") (pinfunction "1_1") (pintype "passive"))
      (node (ref "L13") (pin "2") (pinfunction "2_2") (pintype "passive"))
      (node (ref "U1") (pin "1") (pinfunction "RFI_LF_1") (pintype "passive"))
    )
    (net (code "51") (name "Net-(U1-RFO_LF)") (class "Default")
      (node (ref "C28") (pin "2") (pinfunction "2_2") (pintype "passive"))
      (node (ref "C29") (pin "2") (pinfunction "2_2") (pintype "passive"))
      (node (ref "L1") (pin "2") (pinfunction "2_2") (pintype "passive"))
      (node (ref "U1") (pin "28") (pinfunction "RFO_LF_28") (pintype "passive"))
    )
    (net (code "52") (name "Net-(U1-VR_ANA)") (class "Default")
      (node (ref "C4") (pin "2") (pinfunction "2_2") (pintype "passive"))
      (node (ref "U1") (pin "2") (pinfunction "VR_ANA_2") (pintype "passive"))
    )
    (net (code "53") (name "Net-(U1-VR_DIG)") (class "Default")
      (node (ref "C5") (pin "2") (pinfunction "2_2") (pintype "passive"))
      (node (ref "U1") (pin "4") (pinfunction "VR_DIG_4") (pintype "passive"))
    )
    (net (code "54") (name "Net-(U1-VR_PA)") (class "Default")
      (node (ref "C35") (pin "2") (pinfunction "2_2") (pintype "passive"))
      (node (ref "C7") (pin "2") (pinfunction "2_2") (pintype "passive"))
      (node (ref "C8") (pin "2") (pinfunction "2_2") (pintype "passive"))
      (node (ref "L1") (pin "1") (pinfunction "1_1") (pintype "passive"))
      (node (ref "L2") (pin "2") (pinfunction "2_2") (pintype "passive"))
      (node (ref "U1") (pin "25") (pinfunction "VR_PA_25") (pintype "passive"))
    )
    (net (code "55") (name "Net-(U2-CTRL)") (class "Default")
      (node (ref "C22") (pin "1") (pinfunction "1_1") (pintype "passive"))
      (node (ref "R1") (pin "2") (pinfunction "2_2") (pintype "passive"))
      (node (ref "R2") (pin "1") (pinfunction "1_1") (pintype "passive"))
      (node (ref "U2") (pin "4") (pinfunction "CTRL_4") (pintype "passive"))
    )
    (net (code "56") (name "Net-(U2-RF1)") (class "Default")
      (node (ref "C14") (pin "1") (pinfunction "1_1") (pintype "passive"))
      (node (ref "C15") (pin "2") (pinfunction "2_2") (pintype "passive"))
      (node (ref "L6") (pin "2") (pinfunction "2_2") (pintype "passive"))
      (node (ref "U2") (pin "1") (pinfunction "RF1_1") (pintype "passive"))
    )
    (net (code "57") (name "Net-(U2-RF2)") (class "Default")
      (node (ref "C19") (pin "1") (pinfunction "1_1") (pintype "passive"))
      (node (ref "U2") (pin "3") (pinfunction "RF2_3") (pintype "passive"))
    )
    (net (code "58") (name "Net-(U2-RFC)") (class "Default")
      (node (ref "C20") (pin "2") (pinfunction "2_2") (pintype "passive"))
      (node (ref "U2") (pin "5") (pinfunction "RFC_5") (pintype "passive"))
    )
    (net (code "59") (name "Net-(U2-VDD)") (class "Default")
      (node (ref "C45") (pin "2") (pinfunction "2_2") (pintype "passive"))
      (node (ref "R6") (pin "1") (pinfunction "1_1") (pintype "passive"))
      (node (ref "R7") (pin "1") (pinfunction "1_1") (pintype "passive"))
      (node (ref "U2") (pin "6") (pinfunction "VDD_6") (pintype "passive"))
    )
    (net (code "60") (name "Net-(U4-IN)") (class "Default")
      (node (ref "C19") (pin "2") (pinfunction "2_2") (pintype "passive"))
      (node (ref "U4") (pin "2") (pinfunction "IN_2") (pintype "passive"))
    )
    (net (code "61") (name "Net-(U4-OUT)") (class "Default")
      (node (ref "C18") (pin "1") (pinfunction "1_1") (pintype "passive"))
      (node (ref "U4") (pin "5") (pinfunction "OUT_5") (pintype "passive"))
    )
    (net (code "62") (name "Net-(U5-CTRL)") (class "Default")
      (node (ref "C42") (pin "1") (pinfunction "1_1") (pintype "passive"))
      (node (ref "R11") (pin "1") (pinfunction "1_1") (pintype "passive"))
      (node (ref "U5") (pin "4") (pinfunction "CTRL_4") (pintype "passive"))
    )
    (net (code "63") (name "Net-(U5-RF1)") (class "Default")
      (node (ref "C38") (pin "1") (pinfunction "1_1") (pintype "passive"))
      (node (ref "U5") (pin "1") (pinfunction "RF1_1") (pintype "passive"))
    )
    (net (code "64") (name "Net-(U5-RF2)") (class "Default")
      (node (ref "C33") (pin "1") (pinfunction "1_1") (pintype "passive"))
      (node (ref "C34") (pin "2") (pinfunction "2_2") (pintype "passive"))
      (node (ref "L10") (pin "2") (pinfunction "2_2") (pintype "passive"))
      (node (ref "U5") (pin "3") (pinfunction "RF2_3") (pintype "passive"))
    )
    (net (code "65") (name "Net-(U5-RFC)") (class "Default")
      (node (ref "C39") (pin "2") (pinfunction "2_2") (pintype "passive"))
      (node (ref "U5") (pin "5") (pinfunction "RFC_5") (pintype "passive"))
    )
    (net (code "66") (name "Net-(U5-VDD)") (class "Default")
      (node (ref "C43") (pin "2") (pinfunction "2_2") (pintype "passive"))
      (node (ref "R15") (pin "1") (pinfunction "1_1") (pintype "passive"))
      (node (ref "R8") (pin "1") (pinfunction "1_1") (pintype "passive"))
      (node (ref "U5") (pin "6") (pinfunction "VDD_6") (pintype "passive"))
    )
    (net (code "67") (name "Net-(U6-IN)") (class "Default")
      (node (ref "C38") (pin "2") (pinfunction "2_2") (pintype "passive"))
      (node (ref "U6") (pin "2") (pinfunction "IN_2") (pintype "passive"))
    )
    (net (code "68") (name "Net-(U6-OUT)") (class "Default")
      (node (ref "C36") (pin "1") (pinfunction "1_1") (pintype "passive"))
      (node (ref "U6") (pin "5") (pinfunction "OUT_5") (pintype "passive"))
    )
    (net (code "69") (name "VDD_RF") (class "Default")
      (node (ref "C21") (pin "2") (pinfunction "2_2") (pintype "passive"))
      (node (ref "C23") (pin "2") (pinfunction "2_2") (pintype "passive"))
      (node (ref "C26") (pin "2") (pinfunction "2_2") (pintype "passive"))
      (node (ref "C27") (pin "2") (pinfunction "2_2") (pintype "passive"))
      (node (ref "C3") (pin "2") (pinfunction "2_2") (pintype "passive"))
      (node (ref "R7") (pin "2") (pinfunction "2_2") (pintype "passive"))
      (node (ref "R8") (pin "2") (pinfunction "2_2") (pintype "passive"))
      (node (ref "U1") (pin "14") (pinfunction "VBAT3_14") (pintype "passive"))
      (node (ref "U1") (pin "24") (pinfunction "VBAT2_24") (pintype "passive"))
      (node (ref "U1") (pin "3") (pinfunction "VBAT1_3") (pintype "passive"))
    )
    (net (code "70") (name "unconnected-(Logo1-Pad0)") (class "Default")
      (node (ref "Logo1") (pin "0") (pinfunction "0_0") (pintype "passive"))
    )
    (net (code "71") (name "unconnected-(R5-Pad1)") (class "Default")
      (node (ref "R5") (pin "1") (pinfunction "1_1") (pintype "passive+no_connect"))
    )
    (net (code "72") (name "unconnected-(R5-Pad2)") (class "Default")
      (node (ref "R5") (pin "2") (pinfunction "2_2") (pintype "passive+no_connect"))
    )
    (net (code "73") (name "unconnected-(R5-Pad7)") (class "Default")
      (node (ref "R5") (pin "7") (pinfunction "7_7") (pintype "passive+no_connect"))
    )
    (net (code "74") (name "unconnected-(R5-Pad8)") (class "Default")
      (node (ref "R5") (pin "8") (pinfunction "8_8") (pintype "passive+no_connect"))
    )
    (net (code "75") (name "unconnected-(U1-RFO_HF-Pad22)") (class "Default")
      (node (ref "U1") (pin "22") (pinfunction "RFO_HF_22") (pintype "passive+no_connect"))
    )
  )
)
